# Vapeix_mini_Shield.net
KiCad netlist of a schematic drawn in Altium Designer
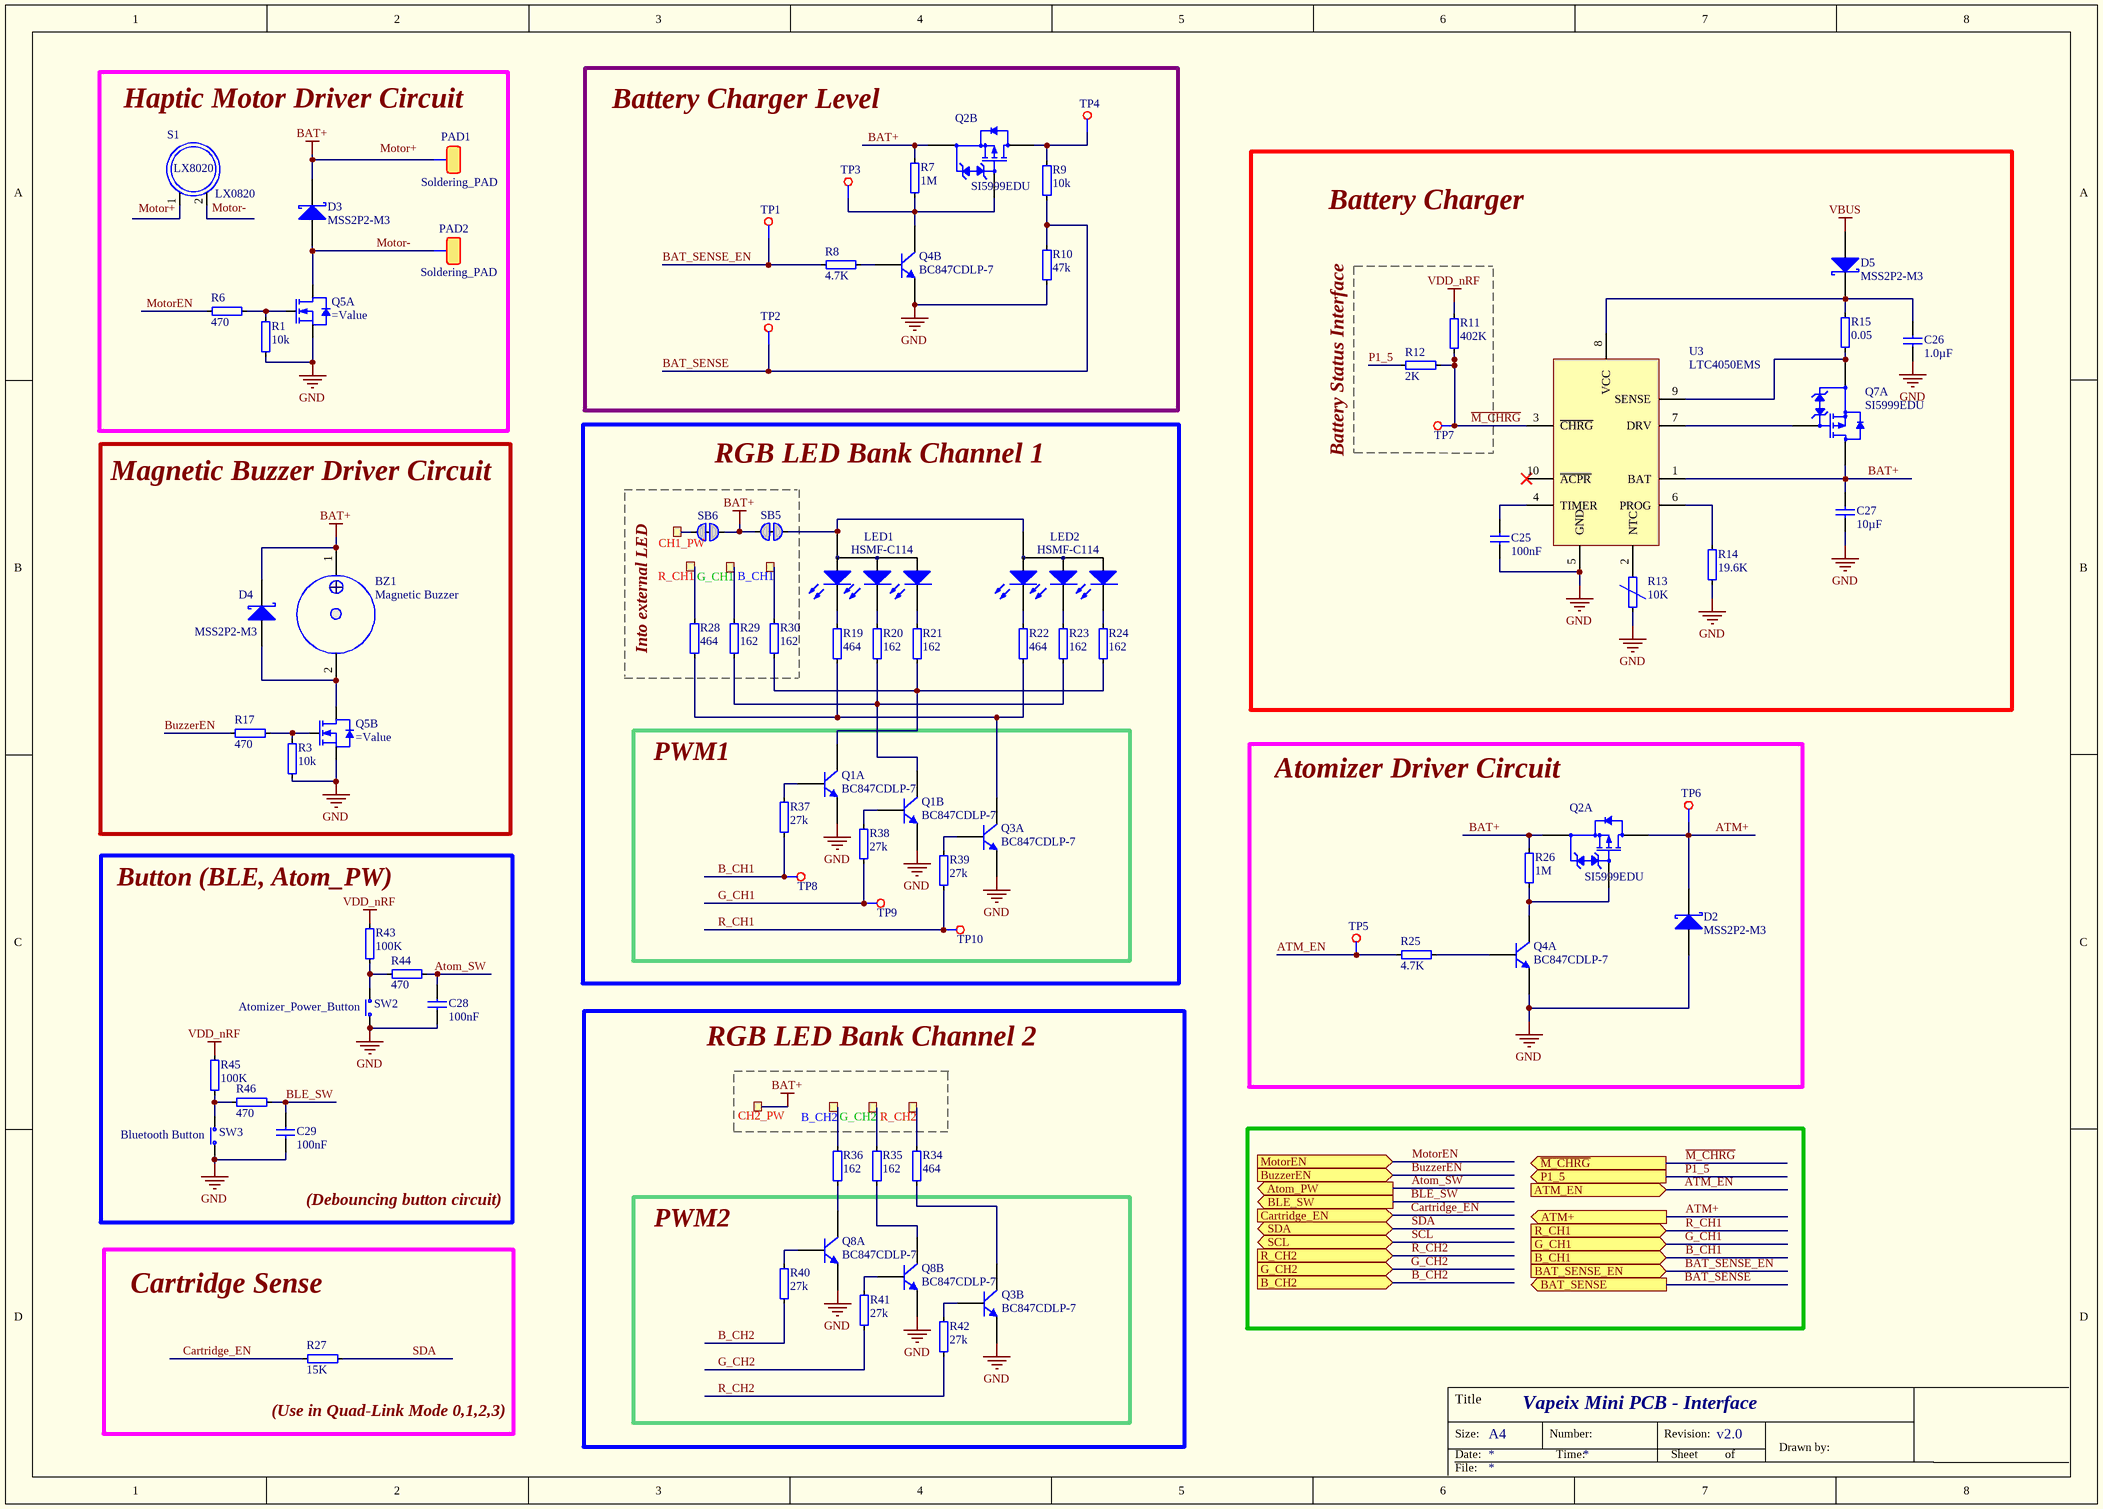
[diagram p0: Vapeix_mini_Shield.SchDoc]

(export (version "E")
  (design (tool "Eeschema 10.0.6"))
  (components
    (comp (ref "BZ1")
      (value "Magnetic Buzzer")
      (footprint "Magnetic Buzzer")
      (description "Audio Indicators & Alerts 6.7 x 3.6mm 3100Hz")
      (fields
        (field (name "MANUFACTURER") "Kobitone")
        (field (name "MANUFACTURER PART NUMBER") "254-EMB73-RO")
      )
      (libsource (lib "VapeixS_LIB") (part "Magnetic Buzzer"))
    )
    (comp (ref "B_CH1")
      (value "TP")
      (footprint "TESTPAD-TH")
      (description "Testpoint, through hole")
      (fields (field (name "PART NUMBER") "Testpoint TH") (field (name "PUBLISHER") "Nordic Semiconductor"))
      (libsource (lib "pca10040") (part "TESTPAD_TH"))
    )
    (comp (ref "B_CH2")
      (value "TP")
      (footprint "TESTPAD-TH")
      (description "Testpoint, through hole")
      (fields (field (name "PART NUMBER") "Testpoint TH") (field (name "PUBLISHER") "Nordic Semiconductor"))
      (libsource (lib "pca10040") (part "TESTPAD_TH"))
    )
    (comp (ref "C25")
      (value "100nF")
      (footprint "C0201")
      (description "CAP CER 0.1UF 10V X5R 0201")
      (fields
        (field (name "PART NUMBER") "C0402-100n")
        (field (name "MANUFACTURER") "Murata Electronics North America")
        (field (name "PUBLISHER") "Nordic Semiconductor")
      )
      (libsource (lib "Nordic Passive DB") (part "CAP"))
    )
    (comp (ref "C26")
      (value "1.0µF")
      (footprint "C0201")
      (description "CAP CER 1UF 16V X5R 0201")
      (fields
        (field (name "MANUFACTURER") "Samsung Electro-Mechanics America, Inc.")
        (field (name "MANUFACTURER PART NUMBER") "CL03A105MO3NRNH")
      )
      (libsource (lib "Nordic Passive DB") (part "CAP"))
    )
    (comp (ref "C27")
      (value "10µF")
      (footprint "R0402")
      (description "CAP CER 10UF 10V X5R 0402")
      (fields
        (field (name "MANUFACTURER") "Samsung Electro-Mechanics America, Inc.")
        (field (name "MANUFACTURER PART NUMBER") "CL05A106MP5NUNC")
        (field (name "PUBLISHER") "Nordic Semiconductor")
      )
      (libsource (lib "Nordic Passive DB") (part "CAP"))
    )
    (comp (ref "C28")
      (value "100nF")
      (footprint "C0201")
      (description "CAP CER 0.1UF 10V X5R 0201")
      (fields
        (field (name "PART NUMBER") "C0402-100n")
        (field (name "MANUFACTURER") "Murata Electronics North America")
        (field (name "PUBLISHER") "Nordic Semiconductor")
      )
      (libsource (lib "Nordic Passive DB") (part "CAP"))
    )
    (comp (ref "C29")
      (value "100nF")
      (footprint "C0201")
      (description "CAP CER 0.1UF 10V X5R 0201")
      (fields
        (field (name "PART NUMBER") "C0402-100n")
        (field (name "MANUFACTURER") "Murata Electronics North America")
        (field (name "PUBLISHER") "Nordic Semiconductor")
      )
      (libsource (lib "Nordic Passive DB") (part "CAP"))
    )
    (comp (ref "CH1_PW")
      (value "TP")
      (footprint "TESTPAD-TH")
      (description "Testpoint, through hole")
      (fields (field (name "PART NUMBER") "Testpoint TH") (field (name "PUBLISHER") "Nordic Semiconductor"))
      (libsource (lib "pca10040") (part "TESTPAD_TH"))
    )
    (comp (ref "CH2_PW")
      (value "TP")
      (footprint "TESTPAD-TH")
      (description "Testpoint, through hole")
      (fields (field (name "PART NUMBER") "Testpoint TH") (field (name "PUBLISHER") "Nordic Semiconductor"))
      (libsource (lib "pca10040") (part "TESTPAD_TH"))
    )
    (comp (ref "D2")
      (value "MSS2P2-M3")
      (footprint "MSS2P2-M3")
      (description "DIODE SCHOTTKY 20V 2A MICROSMP")
      (fields
        (field (name "MANUFACTURER") "Vishay Semiconductor Diodes Division")
        (field (name "MANUFACTURER PART NUMBER") "MSS2P2-M3/89A")
      )
      (libsource (lib "VapeixS_LIB") (part "MSS2P2-M3/89A"))
    )
    (comp (ref "D3")
      (value "MSS2P2-M3")
      (footprint "MSS2P2-M3")
      (description "DIODE SCHOTTKY 20V 2A MICROSMP")
      (fields
        (field (name "MANUFACTURER") "Vishay Semiconductor Diodes Division")
        (field (name "MANUFACTURER PART NUMBER") "MSS2P2-M3/89A")
      )
      (libsource (lib "VapeixS_LIB") (part "MSS2P2-M3/89A"))
    )
    (comp (ref "D4")
      (value "MSS2P2-M3")
      (footprint "MSS2P2-M3")
      (description "DIODE SCHOTTKY 20V 2A MICROSMP")
      (fields
        (field (name "MANUFACTURER") "Vishay Semiconductor Diodes Division")
        (field (name "MANUFACTURER PART NUMBER") "MSS2P2-M3/89A")
      )
      (libsource (lib "VapeixS_LIB") (part "MSS2P2-M3/89A"))
    )
    (comp (ref "D5")
      (value "MSS2P2-M3")
      (footprint "MSS2P2-M3")
      (description "DIODE SCHOTTKY 20V 2A MICROSMP")
      (fields
        (field (name "MANUFACTURER") "Vishay Semiconductor Diodes Division")
        (field (name "MANUFACTURER PART NUMBER") "MSS2P2-M3/89A")
      )
      (libsource (lib "VapeixS_LIB") (part "MSS2P2-M3/89A"))
    )
    (comp (ref "G_CH1")
      (value "TP")
      (footprint "TESTPAD-TH")
      (description "Testpoint, through hole")
      (fields (field (name "PART NUMBER") "Testpoint TH") (field (name "PUBLISHER") "Nordic Semiconductor"))
      (libsource (lib "pca10040") (part "TESTPAD_TH"))
    )
    (comp (ref "G_CH2")
      (value "TP")
      (footprint "TESTPAD-TH")
      (description "Testpoint, through hole")
      (fields (field (name "PART NUMBER") "Testpoint TH") (field (name "PUBLISHER") "Nordic Semiconductor"))
      (libsource (lib "pca10040") (part "TESTPAD_TH"))
    )
    (comp (ref "LED1")
      (value "HSMF-C114")
      (footprint "HSMF-C114")
      (description "LED RGB DIFFUSED 0606 SMD")
      (fields (field (name "MANUFACTURER") "Broadcom Limited"))
      (libsource (lib "VapeixS_LIB") (part "HSMF-C114"))
    )
    (comp (ref "LED2")
      (value "HSMF-C114")
      (footprint "HSMF-C114")
      (description "LED RGB DIFFUSED 0606 SMD")
      (fields (field (name "MANUFACTURER") "Broadcom Limited"))
      (libsource (lib "VapeixS_LIB") (part "HSMF-C114"))
    )
    (comp (ref "PAD1")
      (value "Soldering_PAD")
      (footprint "Soldering_PAD")
      (description "Soldering PAD")
      (libsource (lib "VapeixS_LIB") (part "Soldering_PAD"))
    )
    (comp (ref "PAD2")
      (value "Soldering_PAD")
      (footprint "Soldering_PAD")
      (description "Soldering PAD")
      (libsource (lib "VapeixS_LIB") (part "Soldering_PAD"))
    )
    (comp (ref "Q1")
      (value "BC847CDLP-7")
      (footprint "BC847CDLP-7")
      (description "TRANS 2NPN 45V 0.1A 6DFN")
      (fields (field (name "MANUFACTURER") "Diodes Incorporated"))
      (libsource (lib "") (part "BC847CDLP-7_1"))
    )
    (comp (ref "Q2")
      (value "SI5999EDU")
      (footprint "SI5999EDU")
      (description "MOSFET 2P-CH 20V 6A POWERPAK")
      (fields
        (field (name "MANUFACTURER") "Vishay Siliconix")
        (field (name "MANUFACTURER PART NUMBER") "SI5999EDU-T1-GE3")
      )
      (libsource (lib "VapeixS_LIB") (part "SI5999EDU-T1-GE3"))
    )
    (comp (ref "Q3")
      (value "BC847CDLP-7")
      (footprint "BC847CDLP-7")
      (description "TRANS 2NPN 45V 0.1A 6DFN")
      (fields (field (name "MANUFACTURER") "Diodes Incorporated"))
      (libsource (lib "") (part "BC847CDLP-7_1"))
    )
    (comp (ref "Q4")
      (value "BC847CDLP-7")
      (footprint "BC847CDLP-7")
      (description "TRANS 2NPN 45V 0.1A 6DFN")
      (fields (field (name "MANUFACTURER") "Diodes Incorporated"))
      (libsource (lib "VapeixS_LIB") (part "BC847CDLP-7"))
    )
    (comp (ref "Q5")
      (value "~")
      (footprint "SOT363")
      (description "MOSFET 2N-CH 30V 1A SOT363")
      (fields
        (field (name "MANUFACTURER") "Diodes Incorporated")
        (field (name "MANUFACTURER PART NUMBER") "DMN3190LDW-13")
      )
      (libsource (lib "Vapeix") (part "MOSFET_N_DUAL"))
    )
    (comp (ref "Q7")
      (value "SI5999EDU")
      (footprint "SI5999EDU")
      (description "MOSFET 2P-CH 20V 6A POWERPAK")
      (fields
        (field (name "MANUFACTURER") "Vishay Siliconix")
        (field (name "MANUFACTURER PART NUMBER") "SI5999EDU-T1-GE3")
      )
      (libsource (lib "") (part "SI5999EDU-T1-GE3_2"))
    )
    (comp (ref "Q8")
      (value "BC847CDLP-7")
      (footprint "BC847CDLP-7")
      (description "TRANS 2NPN 45V 0.1A 6DFN")
      (fields (field (name "MANUFACTURER") "Diodes Incorporated"))
      (libsource (lib "") (part "BC847CDLP-7_3"))
    )
    (comp (ref "R1")
      (value "10k")
      (footprint "R0201")
      (description "RES SMD 10K OHM 1% 1/20W 0201")
      (fields
        (field (name "MANUFACTURER") "Panasonic Electronic Components")
        (field (name "MANUFACTURER PART NUMBER") "ERJ-1GEF1002C")
      )
      (libsource (lib "Nordic Passive DB") (part "RES_1"))
    )
    (comp (ref "R3")
      (value "10k")
      (footprint "R0201")
      (description "RES SMD 10K OHM 1% 1/20W 0201")
      (fields
        (field (name "MANUFACTURER") "Panasonic Electronic Components")
        (field (name "MANUFACTURER PART NUMBER") "ERJ-1GEF1002C")
      )
      (libsource (lib "Nordic Passive DB") (part "RES_1"))
    )
    (comp (ref "R6")
      (value "470")
      (footprint "R0201")
      (description "RES SMD 470 OHM 5% 1/20W 0201")
      (fields
        (field (name "MANUFACTURER") "Yageo")
        (field (name "MANUFACTURER PART NUMBER") "RC0201JR-07470RL")
      )
      (libsource (lib "Nordic Passive DB") (part "RES_1"))
    )
    (comp (ref "R7")
      (value "1M")
      (footprint "R0201")
      (description "RES SMD 1M OHM 5% 1/20W 0201")
      (fields
        (field (name "MANUFACTURER") "Yageo")
        (field (name "MANUFACTURER PART NUMBER") "RC0201JR-071ML")
      )
      (libsource (lib "Nordic Passive DB") (part "RES_1"))
    )
    (comp (ref "R8")
      (value "4.7K")
      (footprint "R0201")
      (description "RES SMD 4.7K OHM 1% 1/20W 0201")
      (fields
        (field (name "MANUFACTURER") "Panasonic Electronic Components")
        (field (name "MANUFACTURER PART NUMBER") "ERJ-1GEF4701C")
      )
      (libsource (lib "Nordic Passive DB") (part "RES_1"))
    )
    (comp (ref "R9")
      (value "10k")
      (footprint "R0201")
      (description "RES SMD 10K OHM 1% 1/20W 0201")
      (fields
        (field (name "MANUFACTURER") "Panasonic Electronic Components")
        (field (name "MANUFACTURER PART NUMBER") "ERJ-1GEF1002C")
      )
      (libsource (lib "Nordic Passive DB") (part "RES_1"))
    )
    (comp (ref "R10")
      (value "47k")
      (footprint "R0201")
      (description "RES SMD 47K OHM 1% 1/20W 0201")
      (fields
        (field (name "MANUFACTURER") "Panasonic Electronic Components")
        (field (name "MANUFACTURER PART NUMBER") "ERJ-1GEF4702C")
      )
      (libsource (lib "Nordic Passive DB") (part "RES_1"))
    )
    (comp (ref "R11")
      (value "402K")
      (footprint "R0201")
      (description "RES SMD 402K OHM 1% 1/20W 0201")
      (fields
        (field (name "MANUFACTURER") "Yageo")
        (field (name "MANUFACTURER PART NUMBER") "RC0201FR-07402KL")
      )
      (libsource (lib "Nordic Passive DB") (part "RES_1"))
    )
    (comp (ref "R12")
      (value "2K")
      (footprint "R0201")
      (description "RES SMD 2K OHM 5% 1/20W 0201")
      (fields
        (field (name "MANUFACTURER") "Yageo")
        (field (name "MANUFACTURER PART NUMBER") "RC0201JR-072KL")
      )
      (libsource (lib "Nordic Passive DB") (part "RES_1"))
    )
    (comp (ref "R13")
      (value "10K")
      (footprint "RL0503-5820-97-MS")
      (description "THERMISTOR MINI-SENS NTC 10K OHM")
      (fields
        (field (name "MANUFACTURER") "Stackpole Electronics Inc.")
        (field (name "MANUFACTURER PART NUMBER") "RL0503-5820-97-MS")
      )
      (libsource (lib "VapeixS_LIB") (part "RL0503-5820-97-MS"))
    )
    (comp (ref "R14")
      (value "19.6K")
      (footprint "R0201")
      (description "RES SMD 19.6K OHM 1% 1/20W 0201")
      (fields
        (field (name "MANUFACTURER") "Panasonic Electronic Components")
        (field (name "MANUFACTURER PART NUMBER") "ERJ-1GEF1962C")
      )
      (libsource (lib "Nordic Passive DB") (part "RES_1"))
    )
    (comp (ref "R15")
      (value "0.05")
      (footprint "0805")
      (description "RES SMD 0.05 OHM 1% 1/4W 0805")
      (fields
        (field (name "MANUFACTURER") "Panasonic Electronic Components")
        (field (name "MANUFACTURER PART NUMBER") "ERJ-L06KF50MV")
      )
      (libsource (lib "Nordic Passive DB") (part "RES_1"))
    )
    (comp (ref "R17")
      (value "470")
      (footprint "R0201")
      (description "RES SMD 470 OHM 5% 1/20W 0201")
      (fields
        (field (name "MANUFACTURER") "Yageo")
        (field (name "MANUFACTURER PART NUMBER") "RC0201JR-07470RL")
      )
      (libsource (lib "Nordic Passive DB") (part "RES_1"))
    )
    (comp (ref "R19")
      (value "464")
      (footprint "R0201")
      (description "RES SMD 464 OHM 1% 1/20W 0201")
      (fields
        (field (name "MANUFACTURER") "Panasonic Electronic Components")
        (field (name "MANUFACTURER PART NUMBER") "ERJ-1GEF4640C")
      )
      (libsource (lib "Nordic Passive DB") (part "RES_1"))
    )
    (comp (ref "R20")
      (value "162")
      (footprint "R0201")
      (description "RES SMD 162 OHM 1% 1/20W 0201")
      (fields
        (field (name "MANUFACTURER") "Yageo")
        (field (name "MANUFACTURER PART NUMBER") "RC0201FR-07162RL")
      )
      (libsource (lib "Nordic Passive DB") (part "RES_1"))
    )
    (comp (ref "R21")
      (value "162")
      (footprint "R0201")
      (description "RES SMD 162 OHM 1% 1/20W 0201")
      (fields
        (field (name "MANUFACTURER") "Yageo")
        (field (name "MANUFACTURER PART NUMBER") "RC0201FR-07162RL")
      )
      (libsource (lib "Nordic Passive DB") (part "RES_1"))
    )
    (comp (ref "R22")
      (value "464")
      (footprint "R0201")
      (description "RES SMD 464 OHM 1% 1/20W 0201")
      (fields
        (field (name "MANUFACTURER") "Panasonic Electronic Components")
        (field (name "MANUFACTURER PART NUMBER") "ERJ-1GEF4640C")
      )
      (libsource (lib "Nordic Passive DB") (part "RES_1"))
    )
    (comp (ref "R23")
      (value "162")
      (footprint "R0201")
      (description "RES SMD 162 OHM 1% 1/20W 0201")
      (fields
        (field (name "MANUFACTURER") "Yageo")
        (field (name "MANUFACTURER PART NUMBER") "RC0201FR-07162RL")
      )
      (libsource (lib "Nordic Passive DB") (part "RES_1"))
    )
    (comp (ref "R24")
      (value "162")
      (footprint "R0201")
      (description "RES SMD 162 OHM 1% 1/20W 0201")
      (fields
        (field (name "MANUFACTURER") "Yageo")
        (field (name "MANUFACTURER PART NUMBER") "RC0201FR-07162RL")
      )
      (libsource (lib "Nordic Passive DB") (part "RES_1"))
    )
    (comp (ref "R25")
      (value "4.7K")
      (footprint "R0201")
      (description "RES SMD 4.7K OHM 1% 1/20W 0201")
      (fields
        (field (name "MANUFACTURER") "Panasonic Electronic Components")
        (field (name "MANUFACTURER PART NUMBER") "ERJ-1GEF4701C")
      )
      (libsource (lib "Nordic Passive DB") (part "RES_1"))
    )
    (comp (ref "R26")
      (value "1M")
      (footprint "R0201")
      (description "RES SMD 1M OHM 5% 1/20W 0201")
      (fields
        (field (name "MANUFACTURER") "Yageo")
        (field (name "MANUFACTURER PART NUMBER") "RC0201JR-071ML")
      )
      (libsource (lib "Nordic Passive DB") (part "RES_1"))
    )
    (comp (ref "R27")
      (value "15K")
      (footprint "R0201")
      (description "RES SMD 15K OHM 5% 1/20W 0201")
      (fields
        (field (name "PART NUMBER") "R0402-10k")
        (field (name "MANUFACTURER") "Panasonic Electronic Components")
        (field (name "PUBLISHER") "Nordic Semiconductor")
      )
      (libsource (lib "Nordic Passive DB") (part "RES_1"))
    )
    (comp (ref "R28")
      (value "464")
      (footprint "R0201")
      (description "RES SMD 464 OHM 1% 1/20W 0201")
      (fields
        (field (name "MANUFACTURER") "Panasonic Electronic Components")
        (field (name "MANUFACTURER PART NUMBER") "ERJ-1GEF4640C")
      )
      (libsource (lib "Nordic Passive DB") (part "RES_1"))
    )
    (comp (ref "R29")
      (value "162")
      (footprint "R0201")
      (description "RES SMD 162 OHM 1% 1/20W 0201")
      (fields
        (field (name "MANUFACTURER") "Yageo")
        (field (name "MANUFACTURER PART NUMBER") "RC0201FR-07162RL")
      )
      (libsource (lib "Nordic Passive DB") (part "RES_1"))
    )
    (comp (ref "R30")
      (value "162")
      (footprint "R0201")
      (description "RES SMD 162 OHM 1% 1/20W 0201")
      (fields
        (field (name "MANUFACTURER") "Yageo")
        (field (name "MANUFACTURER PART NUMBER") "RC0201FR-07162RL")
      )
      (libsource (lib "Nordic Passive DB") (part "RES_1"))
    )
    (comp (ref "R34")
      (value "464")
      (footprint "R0201")
      (description "RES SMD 464 OHM 1% 1/20W 0201")
      (fields
        (field (name "MANUFACTURER") "Panasonic Electronic Components")
        (field (name "MANUFACTURER PART NUMBER") "ERJ-1GEF4640C")
      )
      (libsource (lib "Nordic Passive DB") (part "RES_1"))
    )
    (comp (ref "R35")
      (value "162")
      (footprint "R0201")
      (description "RES SMD 162 OHM 1% 1/20W 0201")
      (fields
        (field (name "MANUFACTURER") "Yageo")
        (field (name "MANUFACTURER PART NUMBER") "RC0201FR-07162RL")
      )
      (libsource (lib "Nordic Passive DB") (part "RES_1"))
    )
    (comp (ref "R36")
      (value "162")
      (footprint "R0201")
      (description "RES SMD 162 OHM 1% 1/20W 0201")
      (fields
        (field (name "MANUFACTURER") "Yageo")
        (field (name "MANUFACTURER PART NUMBER") "RC0201FR-07162RL")
      )
      (libsource (lib "Nordic Passive DB") (part "RES_1"))
    )
    (comp (ref "R37")
      (value "27k")
      (footprint "R0201")
      (description "RES SMD 27K OHM 5% 1/20W 0201")
      (fields
        (field (name "MANUFACTURER") "Panasonic Electronic Components")
        (field (name "MANUFACTURER PART NUMBER") "ERJ-1GEJ273C")
      )
      (libsource (lib "Nordic Passive DB") (part "RES_1"))
    )
    (comp (ref "R38")
      (value "27k")
      (footprint "R0201")
      (description "RES SMD 27K OHM 5% 1/20W 0201")
      (fields
        (field (name "MANUFACTURER") "Panasonic Electronic Components")
        (field (name "MANUFACTURER PART NUMBER") "ERJ-1GEJ273C")
      )
      (libsource (lib "Nordic Passive DB") (part "RES_1"))
    )
    (comp (ref "R39")
      (value "27k")
      (footprint "R0201")
      (description "RES SMD 27K OHM 5% 1/20W 0201")
      (fields
        (field (name "MANUFACTURER") "Panasonic Electronic Components")
        (field (name "MANUFACTURER PART NUMBER") "ERJ-1GEJ273C")
      )
      (libsource (lib "Nordic Passive DB") (part "RES_1"))
    )
    (comp (ref "R40")
      (value "27k")
      (footprint "R0201")
      (description "RES SMD 27K OHM 5% 1/20W 0201")
      (fields
        (field (name "MANUFACTURER") "Panasonic Electronic Components")
        (field (name "MANUFACTURER PART NUMBER") "ERJ-1GEJ273C")
      )
      (libsource (lib "Nordic Passive DB") (part "RES_1"))
    )
    (comp (ref "R41")
      (value "27k")
      (footprint "R0201")
      (description "RES SMD 27K OHM 5% 1/20W 0201")
      (fields
        (field (name "MANUFACTURER") "Panasonic Electronic Components")
        (field (name "MANUFACTURER PART NUMBER") "ERJ-1GEJ273C")
      )
      (libsource (lib "Nordic Passive DB") (part "RES_1"))
    )
    (comp (ref "R42")
      (value "27k")
      (footprint "R0201")
      (description "RES SMD 27K OHM 5% 1/20W 0201")
      (fields
        (field (name "MANUFACTURER") "Panasonic Electronic Components")
        (field (name "MANUFACTURER PART NUMBER") "ERJ-1GEJ273C")
      )
      (libsource (lib "Nordic Passive DB") (part "RES_1"))
    )
    (comp (ref "R43")
      (value "100K")
      (footprint "R0201")
      (description "RES SMD 100K OHM 5% 1/20W 0201")
      (fields
        (field (name "MANUFACTURER") "Yageo")
        (field (name "MANUFACTURER PART NUMBER") "RC0201JR-07100KL")
      )
      (libsource (lib "Nordic Passive DB") (part "RES_1"))
    )
    (comp (ref "R44")
      (value "470")
      (footprint "R0201")
      (description "RES SMD 470 OHM 5% 1/20W 0201")
      (fields
        (field (name "MANUFACTURER") "Yageo")
        (field (name "MANUFACTURER PART NUMBER") "RC0201JR-07470RL")
      )
      (libsource (lib "Nordic Passive DB") (part "RES_1"))
    )
    (comp (ref "R45")
      (value "100K")
      (footprint "R0201")
      (description "RES SMD 100K OHM 5% 1/20W 0201")
      (fields
        (field (name "MANUFACTURER") "Yageo")
        (field (name "MANUFACTURER PART NUMBER") "RC0201JR-07100KL")
      )
      (libsource (lib "Nordic Passive DB") (part "RES_1"))
    )
    (comp (ref "R46")
      (value "470")
      (footprint "R0201")
      (description "RES SMD 470 OHM 5% 1/20W 0201")
      (fields
        (field (name "MANUFACTURER") "Yageo")
        (field (name "MANUFACTURER PART NUMBER") "RC0201JR-07470RL")
      )
      (libsource (lib "Nordic Passive DB") (part "RES_1"))
    )
    (comp (ref "R_CH1")
      (value "TP")
      (footprint "TESTPAD-TH")
      (description "Testpoint, through hole")
      (fields (field (name "PART NUMBER") "Testpoint TH") (field (name "PUBLISHER") "Nordic Semiconductor"))
      (libsource (lib "pca10040") (part "TESTPAD_TH"))
    )
    (comp (ref "R_CH2")
      (value "TP")
      (footprint "TESTPAD-TH")
      (description "Testpoint, through hole")
      (fields (field (name "PART NUMBER") "Testpoint TH") (field (name "PUBLISHER") "Nordic Semiconductor"))
      (libsource (lib "pca10040") (part "TESTPAD_TH"))
    )
    (comp (ref "S1")
      (value "LX0820")
      (footprint "LX0820L20140926-01")
      (description "LX0820L20140926-01")
      (libsource (lib "VapeixS_LIB") (part "LX0820"))
    )
    (comp (ref "SB5")
      (value "Solderbridge")
      (footprint "Solderbridge_Shorted")
      (description "Shorted Solderbridge")
      (fields
        (field (name "PART NUMBER") "Solderbridge Shorted")
        (field (name "PUBLISHER") "Nordic Semiconductor")
      )
      (libsource (lib "Nordic Passive DB") (part "SOLDERBRIDGE_SHORTED"))
    )
    (comp (ref "SB6")
      (value "Solderbridge")
      (footprint "Solderbridge_Shorted")
      (description "Shorted Solderbridge")
      (fields
        (field (name "PART NUMBER") "Solderbridge Shorted")
        (field (name "PUBLISHER") "Nordic Semiconductor")
      )
      (libsource (lib "Nordic Passive DB") (part "SOLDERBRIDGE_SHORTED"))
    )
    (comp (ref "SW2")
      (value "Atomizer_Power_Button")
      (footprint "ALPS_SKHUxxx010_WO_GND")
      (description "ALPS - SKHUALE010 - Tactile Switch, SPNO, SMD, 6.5x6.2x2.5mm")
      (fields
        (field (name "PART NUMBER") "ALPS_SKHUALE010")
        (field (name "MANUFACTURER") "Alps")
        (field (name "PUBLISHER") "Nordic Semiconductor")
      )
      (libsource (lib "Nordic Discrete DB") (part "SW-PB"))
    )
    (comp (ref "SW3")
      (value "Bluetooth Button")
      (footprint "ALPS_SKHUxxx010_WO_GND")
      (description "ALPS - SKHUALE010 - Tactile Switch, SPNO, SMD, 6.5x6.2x2.5mm")
      (fields
        (field (name "PART NUMBER") "ALPS_SKHUALE010")
        (field (name "MANUFACTURER") "Alps")
        (field (name "PUBLISHER") "Nordic Semiconductor")
      )
      (libsource (lib "Nordic Discrete DB") (part "SW-PB"))
    )
    (comp (ref "TP1")
      (value "TP")
      (footprint "TP")
      (description "TEST POINT")
      (libsource (lib "") (part "TP_1"))
    )
    (comp (ref "TP2")
      (value "TP")
      (footprint "TP")
      (description "TEST POINT")
      (libsource (lib "") (part "TP_1"))
    )
    (comp (ref "TP3")
      (value "TP")
      (footprint "TP")
      (description "TEST POINT")
      (libsource (lib "") (part "TP_1"))
    )
    (comp (ref "TP4")
      (value "TP")
      (footprint "TP")
      (description "TEST POINT")
      (libsource (lib "") (part "TP_1"))
    )
    (comp (ref "TP5")
      (value "TP")
      (footprint "TP")
      (description "TEST POINT")
      (libsource (lib "VapeixS_LIB") (part "TP"))
    )
    (comp (ref "TP6")
      (value "TP")
      (footprint "TP")
      (description "TEST POINT")
      (libsource (lib "VapeixS_LIB") (part "TP"))
    )
    (comp (ref "TP7")
      (value "TP")
      (footprint "TP")
      (description "TEST POINT")
      (libsource (lib "") (part "TP_3"))
    )
    (comp (ref "TP8")
      (value "TP")
      (footprint "TP")
      (description "TEST POINT")
      (libsource (lib "") (part "TP_2"))
    )
    (comp (ref "TP9")
      (value "TP")
      (footprint "TP")
      (description "TEST POINT")
      (libsource (lib "") (part "TP_2"))
    )
    (comp (ref "TP10")
      (value "TP")
      (footprint "TP")
      (description "TEST POINT")
      (libsource (lib "") (part "TP_2"))
    )
    (comp (ref "U3")
      (value "LTC4050EMS")
      (footprint "LTC4050EMS")
      (description "IC BATT CHRG CNTRL LI-ION 10MSOP")
      (fields
        (field (name "MANUFACTURER") "Linear Technology")
        (field (name "MANUFACTURER PART NUMBER") "LTC4050EMS-4.2#PBF")
      )
      (libsource (lib "VapeixS_LIB") (part "LTC4050EMS-4.1#PBF"))
    )
  )
  (nets
    (net (code "4") (name "/ATM+") (class "Default")
      (node (ref "D2") (pin "2") (pinfunction "K_2") (pintype "passive"))
      (node (ref "Q2") (pin "7") (pinfunction "D1_7") (pintype "passive"))
      (node (ref "TP6") (pin "1") (pinfunction "TP_1") (pintype "passive"))
    )
    (net (code "5") (name "/ATM_EN") (class "Default")
      (node (ref "R25") (pin "2") (pinfunction "2_2") (pintype "passive"))
      (node (ref "TP5") (pin "1") (pinfunction "TP_1") (pintype "passive"))
    )
    (net (code "6") (name "/Atom_SW") (class "Default")
      (node (ref "C28") (pin "1") (pinfunction "1_1") (pintype "passive"))
      (node (ref "R44") (pin "1") (pinfunction "1_1") (pintype "passive"))
    )
    (net (code "8") (name "/BAT_SENSE") (class "Default")
      (node (ref "R10") (pin "2") (pinfunction "2_2") (pintype "passive"))
      (node (ref "R9") (pin "1") (pinfunction "1_1") (pintype "passive"))
      (node (ref "TP2") (pin "1") (pinfunction "TP_1") (pintype "passive"))
    )
    (net (code "9") (name "/BAT_SENSE_EN") (class "Default")
      (node (ref "R8") (pin "2") (pinfunction "2_2") (pintype "passive"))
      (node (ref "TP1") (pin "1") (pinfunction "TP_1") (pintype "passive"))
    )
    (net (code "10") (name "/BLE_SW") (class "Default")
      (node (ref "C29") (pin "1") (pinfunction "1_1") (pintype "passive"))
      (node (ref "R46") (pin "1") (pinfunction "1_1") (pintype "passive"))
    )
    (net (code "11") (name "/B_CH1") (class "Default")
      (node (ref "R37") (pin "2") (pinfunction "2_2") (pintype "passive"))
      (node (ref "TP8") (pin "1") (pinfunction "TP_1") (pintype "passive"))
    )
    (net (code "12") (name "/B_CH2") (class "Default")
      (node (ref "R40") (pin "2") (pinfunction "2_2") (pintype "passive"))
    )
    (net (code "17") (name "/BuzzerEN") (class "Default")
      (node (ref "R17") (pin "2") (pinfunction "2_2") (pintype "passive"))
    )
    (net (code "19") (name "/Cartridge_EN") (class "Default")
      (node (ref "R27") (pin "2") (pinfunction "2_2") (pintype "passive"))
    )
    (net (code "20") (name "/G_CH1") (class "Default")
      (node (ref "R38") (pin "2") (pinfunction "2_2") (pintype "passive"))
      (node (ref "TP9") (pin "1") (pinfunction "TP_1") (pintype "passive"))
    )
    (net (code "21") (name "/G_CH2") (class "Default")
      (node (ref "R41") (pin "2") (pinfunction "2_2") (pintype "passive"))
    )
    (net (code "26") (name "/Motor-") (class "Default")
      (node (ref "D3") (pin "1") (pinfunction "A_1") (pintype "passive"))
      (node (ref "PAD2") (pin "1") (pinfunction "TP_1") (pintype "passive"))
      (node (ref "Q5") (pin "6") (pinfunction "D1_6") (pintype "passive"))
    )
    (net (code "27") (name "/MotorEN") (class "Default")
      (node (ref "R6") (pin "2") (pinfunction "2_2") (pintype "passive"))
    )
    (net (code "28") (name "/P1_5") (class "Default")
      (node (ref "R12") (pin "1") (pinfunction "1_1") (pintype "passive"))
    )
    (net (code "33") (name "/R_CH1") (class "Default")
      (node (ref "R39") (pin "2") (pinfunction "2_2") (pintype "passive"))
      (node (ref "TP10") (pin "1") (pinfunction "TP_1") (pintype "passive"))
    )
    (net (code "34") (name "/R_CH2") (class "Default")
      (node (ref "R42") (pin "2") (pinfunction "2_2") (pintype "passive"))
    )
    (net (code "36") (name "/SDA") (class "Default")
      (node (ref "R27") (pin "1") (pinfunction "1_1") (pintype "passive"))
    )
    (net (code "37") (name "/~{M_CHRG}") (class "Default")
      (node (ref "R11") (pin "2") (pinfunction "2_2") (pintype "passive"))
      (node (ref "R12") (pin "2") (pinfunction "2_2") (pintype "passive"))
      (node (ref "TP7") (pin "1") (pinfunction "TP_1") (pintype "passive"))
      (node (ref "U3") (pin "3") (pinfunction "~{CHRG}_3") (pintype "passive"))
    )
    (net (code "38") (name "BAT+") (class "Default")
      (node (ref "BZ1") (pin "1") (pinfunction "P_1") (pintype "passive"))
      (node (ref "C27") (pin "2") (pinfunction "2_2") (pintype "passive"))
      (node (ref "CH2_PW") (pin "1") (pinfunction "1_1") (pintype "passive"))
      (node (ref "D3") (pin "2") (pinfunction "K_2") (pintype "passive"))
      (node (ref "D4") (pin "2") (pinfunction "K_2") (pintype "passive"))
      (node (ref "PAD1") (pin "1") (pinfunction "TP_1") (pintype "passive"))
      (node (ref "Q2") (pin "1") (pinfunction "S1_1") (pintype "passive"))
      (node (ref "Q2") (pin "3") (pinfunction "S2_3") (pintype "passive"))
      (node (ref "Q7") (pin "7") (pinfunction "D1_7") (pintype "passive"))
      (node (ref "R26") (pin "2") (pinfunction "2_2") (pintype "passive"))
      (node (ref "R7") (pin "2") (pinfunction "2_2") (pintype "passive"))
      (node (ref "SB5") (pin "2") (pinfunction "1_2") (pintype "passive"))
      (node (ref "SB6") (pin "2") (pinfunction "1_2") (pintype "passive"))
      (node (ref "U3") (pin "1") (pinfunction "BAT_1") (pintype "passive"))
    )
    (net (code "39") (name "GND") (class "Default")
      (node (ref "C25") (pin "2") (pinfunction "2_2") (pintype "passive"))
      (node (ref "C26") (pin "1") (pinfunction "1_1") (pintype "passive"))
      (node (ref "C27") (pin "1") (pinfunction "1_1") (pintype "passive"))
      (node (ref "C28") (pin "2") (pinfunction "2_2") (pintype "passive"))
      (node (ref "C29") (pin "2") (pinfunction "2_2") (pintype "passive"))
      (node (ref "D2") (pin "1") (pinfunction "A_1") (pintype "passive"))
      (node (ref "Q1") (pin "1") (pinfunction "E1_1") (pintype "passive"))
      (node (ref "Q1") (pin "4") (pinfunction "E2_4") (pintype "passive"))
      (node (ref "Q3") (pin "1") (pinfunction "E1_1") (pintype "passive"))
      (node (ref "Q3") (pin "4") (pinfunction "E2_4") (pintype "passive"))
      (node (ref "Q4") (pin "1") (pinfunction "E1_1") (pintype "passive"))
      (node (ref "Q4") (pin "4") (pinfunction "E2_4") (pintype "passive"))
      (node (ref "Q5") (pin "1") (pinfunction "S1_1") (pintype "passive"))
      (node (ref "Q5") (pin "4") (pinfunction "S2_4") (pintype "passive"))
      (node (ref "Q8") (pin "1") (pinfunction "E1_1") (pintype "passive"))
      (node (ref "Q8") (pin "4") (pinfunction "E2_4") (pintype "passive"))
      (node (ref "R1") (pin "1") (pinfunction "1_1") (pintype "passive"))
      (node (ref "R10") (pin "1") (pinfunction "1_1") (pintype "passive"))
      (node (ref "R13") (pin "2") (pinfunction "2_2") (pintype "passive"))
      (node (ref "R14") (pin "2") (pinfunction "2_2") (pintype "passive"))
      (node (ref "R3") (pin "1") (pinfunction "1_1") (pintype "passive"))
      (node (ref "SW2") (pin "1") (pinfunction "N.O_1") (pintype "passive"))
      (node (ref "SW3") (pin "1") (pinfunction "N.O_1") (pintype "passive"))
      (node (ref "U3") (pin "5") (pinfunction "GND_5") (pintype "passive"))
    )
    (net (code "40") (name "Net-(BZ1-M)") (class "Default")
      (node (ref "BZ1") (pin "2") (pinfunction "M_2") (pintype "passive"))
      (node (ref "D4") (pin "1") (pinfunction "A_1") (pintype "passive"))
      (node (ref "Q5") (pin "3") (pinfunction "D2_3") (pintype "passive"))
    )
    (net (code "41") (name "Net-(B_CH1-Pad1)") (class "Default")
      (node (ref "B_CH1") (pin "1") (pinfunction "1_1") (pintype "passive"))
      (node (ref "R30") (pin "1") (pinfunction "1_1") (pintype "passive"))
    )
    (net (code "42") (name "Net-(B_CH2-Pad1)") (class "Default")
      (node (ref "B_CH2") (pin "1") (pinfunction "1_1") (pintype "passive"))
      (node (ref "R36") (pin "1") (pinfunction "1_1") (pintype "passive"))
    )
    (net (code "43") (name "Net-(D5-K)") (class "Default")
      (node (ref "C26") (pin "2") (pinfunction "2_2") (pintype "passive"))
      (node (ref "D5") (pin "2") (pinfunction "K_2") (pintype "passive"))
      (node (ref "R15") (pin "1") (pinfunction "1_1") (pintype "passive"))
      (node (ref "U3") (pin "8") (pinfunction "VCC_8") (pintype "passive"))
    )
    (net (code "44") (name "Net-(G_CH1-Pad1)") (class "Default")
      (node (ref "G_CH1") (pin "1") (pinfunction "1_1") (pintype "passive"))
      (node (ref "R29") (pin "1") (pinfunction "1_1") (pintype "passive"))
    )
    (net (code "45") (name "Net-(G_CH2-Pad1)") (class "Default")
      (node (ref "G_CH2") (pin "1") (pinfunction "1_1") (pintype "passive"))
      (node (ref "R35") (pin "1") (pinfunction "1_1") (pintype "passive"))
    )
    (net (code "46") (name "Net-(LED1-ANODE)") (class "Default")
      (node (ref "LED1") (pin "1") (pinfunction "ANODE_1") (pintype "passive"))
      (node (ref "LED2") (pin "1") (pinfunction "ANODE_1") (pintype "passive"))
      (node (ref "SB5") (pin "1") (pinfunction "0_1") (pintype "passive"))
    )
    (net (code "47") (name "Net-(LED1-BLUE)") (class "Default")
      (node (ref "LED1") (pin "4") (pinfunction "BLUE_4") (pintype "passive"))
      (node (ref "R21") (pin "1") (pinfunction "1_1") (pintype "passive"))
    )
    (net (code "48") (name "Net-(LED1-GREEN)") (class "Default")
      (node (ref "LED1") (pin "3") (pinfunction "GREEN_3") (pintype "passive"))
      (node (ref "R20") (pin "1") (pinfunction "1_1") (pintype "passive"))
    )
    (net (code "49") (name "Net-(LED1-RED)") (class "Default")
      (node (ref "LED1") (pin "2") (pinfunction "RED_2") (pintype "passive"))
      (node (ref "R19") (pin "1") (pinfunction "1_1") (pintype "passive"))
    )
    (net (code "50") (name "Net-(LED2-BLUE)") (class "Default")
      (node (ref "LED2") (pin "4") (pinfunction "BLUE_4") (pintype "passive"))
      (node (ref "R24") (pin "1") (pinfunction "1_1") (pintype "passive"))
    )
    (net (code "51") (name "Net-(LED2-GREEN)") (class "Default")
      (node (ref "LED2") (pin "3") (pinfunction "GREEN_3") (pintype "passive"))
      (node (ref "R23") (pin "1") (pinfunction "1_1") (pintype "passive"))
    )
    (net (code "52") (name "Net-(LED2-RED)") (class "Default")
      (node (ref "LED2") (pin "2") (pinfunction "RED_2") (pintype "passive"))
      (node (ref "R22") (pin "1") (pinfunction "1_1") (pintype "passive"))
    )
    (net (code "53") (name "Net-(Q1A-B1)") (class "Default")
      (node (ref "Q1") (pin "2") (pinfunction "B1_2") (pintype "passive"))
      (node (ref "R37") (pin "1") (pinfunction "1_1") (pintype "passive"))
    )
    (net (code "54") (name "Net-(Q1A-C1)") (class "Default")
      (node (ref "Q1") (pin "3") (pinfunction "C1_3") (pintype "passive"))
      (node (ref "R21") (pin "2") (pinfunction "2_2") (pintype "passive"))
      (node (ref "R24") (pin "2") (pinfunction "2_2") (pintype "passive"))
      (node (ref "R30") (pin "2") (pinfunction "2_2") (pintype "passive"))
    )
    (net (code "55") (name "Net-(Q1B-B2)") (class "Default")
      (node (ref "Q1") (pin "5") (pinfunction "B2_5") (pintype "passive"))
      (node (ref "R38") (pin "1") (pinfunction "1_1") (pintype "passive"))
    )
    (net (code "56") (name "Net-(Q1B-C2)") (class "Default")
      (node (ref "Q1") (pin "6") (pinfunction "C2_6") (pintype "passive"))
      (node (ref "R20") (pin "2") (pinfunction "2_2") (pintype "passive"))
      (node (ref "R23") (pin "2") (pinfunction "2_2") (pintype "passive"))
      (node (ref "R29") (pin "2") (pinfunction "2_2") (pintype "passive"))
    )
    (net (code "57") (name "Net-(Q2A-G1)") (class "Default")
      (node (ref "Q2") (pin "2") (pinfunction "G1_2") (pintype "passive"))
      (node (ref "Q4") (pin "3") (pinfunction "C1_3") (pintype "passive"))
      (node (ref "R26") (pin "1") (pinfunction "1_1") (pintype "passive"))
    )
    (net (code "58") (name "Net-(Q2B-D2)") (class "Default")
      (node (ref "Q2") (pin "5") (pinfunction "D2_5") (pintype "passive"))
      (node (ref "R9") (pin "2") (pinfunction "2_2") (pintype "passive"))
      (node (ref "TP4") (pin "1") (pinfunction "TP_1") (pintype "passive"))
    )
    (net (code "59") (name "Net-(Q2B-G2)") (class "Default")
      (node (ref "Q2") (pin "4") (pinfunction "G2_4") (pintype "passive"))
      (node (ref "Q4") (pin "6") (pinfunction "C2_6") (pintype "passive"))
      (node (ref "R7") (pin "1") (pinfunction "1_1") (pintype "passive"))
      (node (ref "TP3") (pin "1") (pinfunction "TP_1") (pintype "passive"))
    )
    (net (code "60") (name "Net-(Q3A-B1)") (class "Default")
      (node (ref "Q3") (pin "2") (pinfunction "B1_2") (pintype "passive"))
      (node (ref "R39") (pin "1") (pinfunction "1_1") (pintype "passive"))
    )
    (net (code "61") (name "Net-(Q3A-C1)") (class "Default")
      (node (ref "Q3") (pin "3") (pinfunction "C1_3") (pintype "passive"))
      (node (ref "R19") (pin "2") (pinfunction "2_2") (pintype "passive"))
      (node (ref "R22") (pin "2") (pinfunction "2_2") (pintype "passive"))
      (node (ref "R28") (pin "2") (pinfunction "2_2") (pintype "passive"))
    )
    (net (code "62") (name "Net-(Q3B-B2)") (class "Default")
      (node (ref "Q3") (pin "5") (pinfunction "B2_5") (pintype "passive"))
      (node (ref "R42") (pin "1") (pinfunction "1_1") (pintype "passive"))
    )
    (net (code "63") (name "Net-(Q3B-C2)") (class "Default")
      (node (ref "Q3") (pin "6") (pinfunction "C2_6") (pintype "passive"))
      (node (ref "R34") (pin "2") (pinfunction "2_2") (pintype "passive"))
    )
    (net (code "64") (name "Net-(Q4A-B1)") (class "Default")
      (node (ref "Q4") (pin "2") (pinfunction "B1_2") (pintype "passive"))
      (node (ref "R25") (pin "1") (pinfunction "1_1") (pintype "passive"))
    )
    (net (code "65") (name "Net-(Q4B-B2)") (class "Default")
      (node (ref "Q4") (pin "5") (pinfunction "B2_5") (pintype "passive"))
      (node (ref "R8") (pin "1") (pinfunction "1_1") (pintype "passive"))
    )
    (net (code "66") (name "Net-(Q5A-G1)") (class "Default")
      (node (ref "Q5") (pin "2") (pinfunction "G1_2") (pintype "passive"))
      (node (ref "R1") (pin "2") (pinfunction "2_2") (pintype "passive"))
      (node (ref "R6") (pin "1") (pinfunction "1_1") (pintype "passive"))
    )
    (net (code "67") (name "Net-(Q5B-G2)") (class "Default")
      (node (ref "Q5") (pin "5") (pinfunction "G2_5") (pintype "passive"))
      (node (ref "R17") (pin "1") (pinfunction "1_1") (pintype "passive"))
      (node (ref "R3") (pin "2") (pinfunction "2_2") (pintype "passive"))
    )
    (net (code "68") (name "Net-(Q7A-G1)") (class "Default")
      (node (ref "Q7") (pin "2") (pinfunction "G1_2") (pintype "passive"))
      (node (ref "U3") (pin "7") (pinfunction "DRV_7") (pintype "passive"))
    )
    (net (code "69") (name "Net-(Q7A-S1)") (class "Default")
      (node (ref "Q7") (pin "1") (pinfunction "S1_1") (pintype "passive"))
      (node (ref "R15") (pin "2") (pinfunction "2_2") (pintype "passive"))
      (node (ref "U3") (pin "9") (pinfunction "SENSE_9") (pintype "passive"))
    )
    (net (code "70") (name "Net-(Q8A-B1)") (class "Default")
      (node (ref "Q8") (pin "2") (pinfunction "B1_2") (pintype "passive"))
      (node (ref "R40") (pin "1") (pinfunction "1_1") (pintype "passive"))
    )
    (net (code "71") (name "Net-(Q8A-C1)") (class "Default")
      (node (ref "Q8") (pin "3") (pinfunction "C1_3") (pintype "passive"))
      (node (ref "R36") (pin "2") (pinfunction "2_2") (pintype "passive"))
    )
    (net (code "72") (name "Net-(Q8B-B2)") (class "Default")
      (node (ref "Q8") (pin "5") (pinfunction "B2_5") (pintype "passive"))
      (node (ref "R41") (pin "1") (pinfunction "1_1") (pintype "passive"))
    )
    (net (code "73") (name "Net-(Q8B-C2)") (class "Default")
      (node (ref "Q8") (pin "6") (pinfunction "C2_6") (pintype "passive"))
      (node (ref "R35") (pin "2") (pinfunction "2_2") (pintype "passive"))
    )
    (net (code "74") (name "Net-(R28-Pad1)") (class "Default")
      (node (ref "R28") (pin "1") (pinfunction "1_1") (pintype "passive"))
      (node (ref "R_CH1") (pin "1") (pinfunction "1_1") (pintype "passive"))
    )
    (net (code "75") (name "Net-(R34-Pad1)") (class "Default")
      (node (ref "R34") (pin "1") (pinfunction "1_1") (pintype "passive"))
      (node (ref "R_CH2") (pin "1") (pinfunction "1_1") (pintype "passive"))
    )
    (net (code "76") (name "Net-(SB6-0)") (class "Default")
      (node (ref "CH1_PW") (pin "1") (pinfunction "1_1") (pintype "passive"))
      (node (ref "SB6") (pin "1") (pinfunction "0_1") (pintype "passive"))
    )
    (net (code "77") (name "Net-(SW2-COM)") (class "Default")
      (node (ref "R43") (pin "1") (pinfunction "1_1") (pintype "passive"))
      (node (ref "R44") (pin "2") (pinfunction "2_2") (pintype "passive"))
      (node (ref "SW2") (pin "2") (pinfunction "COM_2") (pintype "passive"))
    )
    (net (code "78") (name "Net-(SW3-COM)") (class "Default")
      (node (ref "R45") (pin "1") (pinfunction "1_1") (pintype "passive"))
      (node (ref "R46") (pin "2") (pinfunction "2_2") (pintype "passive"))
      (node (ref "SW3") (pin "2") (pinfunction "COM_2") (pintype "passive"))
    )
    (net (code "79") (name "Net-(U3-NTC)") (class "Default")
      (node (ref "R13") (pin "1") (pinfunction "1_1") (pintype "passive"))
      (node (ref "U3") (pin "2") (pinfunction "NTC_2") (pintype "passive"))
    )
    (net (code "80") (name "Net-(U3-PROG)") (class "Default")
      (node (ref "R14") (pin "1") (pinfunction "1_1") (pintype "passive"))
      (node (ref "U3") (pin "6") (pinfunction "PROG_6") (pintype "passive"))
    )
    (net (code "81") (name "Net-(U3-TIMER)") (class "Default")
      (node (ref "C25") (pin "1") (pinfunction "1_1") (pintype "passive"))
      (node (ref "U3") (pin "4") (pinfunction "TIMER_4") (pintype "passive"))
    )
    (net (code "82") (name "VBUS") (class "Default")
      (node (ref "D5") (pin "1") (pinfunction "A_1") (pintype "passive"))
    )
    (net (code "83") (name "VDD_nRF") (class "Default")
      (node (ref "R11") (pin "1") (pinfunction "1_1") (pintype "passive"))
      (node (ref "R43") (pin "2") (pinfunction "2_2") (pintype "passive"))
      (node (ref "R45") (pin "2") (pinfunction "2_2") (pintype "passive"))
    )
    (net (code "84") (name "unconnected-(S1-GND-Pad2)") (class "Default")
      (node (ref "S1") (pin "2") (pinfunction "GND_2") (pintype "passive"))
    )
    (net (code "85") (name "unconnected-(S1-PW-Pad1)") (class "Default")
      (node (ref "S1") (pin "1") (pinfunction "PW_1") (pintype "passive"))
    )
    (net (code "86") (name "unconnected-(U3-~{ACPR}-Pad10)") (class "Default")
      (node (ref "U3") (pin "10") (pinfunction "~{ACPR}_10") (pintype "passive+no_connect"))
    )
  )
)
